# main_on_hydrolib.net
KiCad netlist of a schematic drawn in Altium Designer
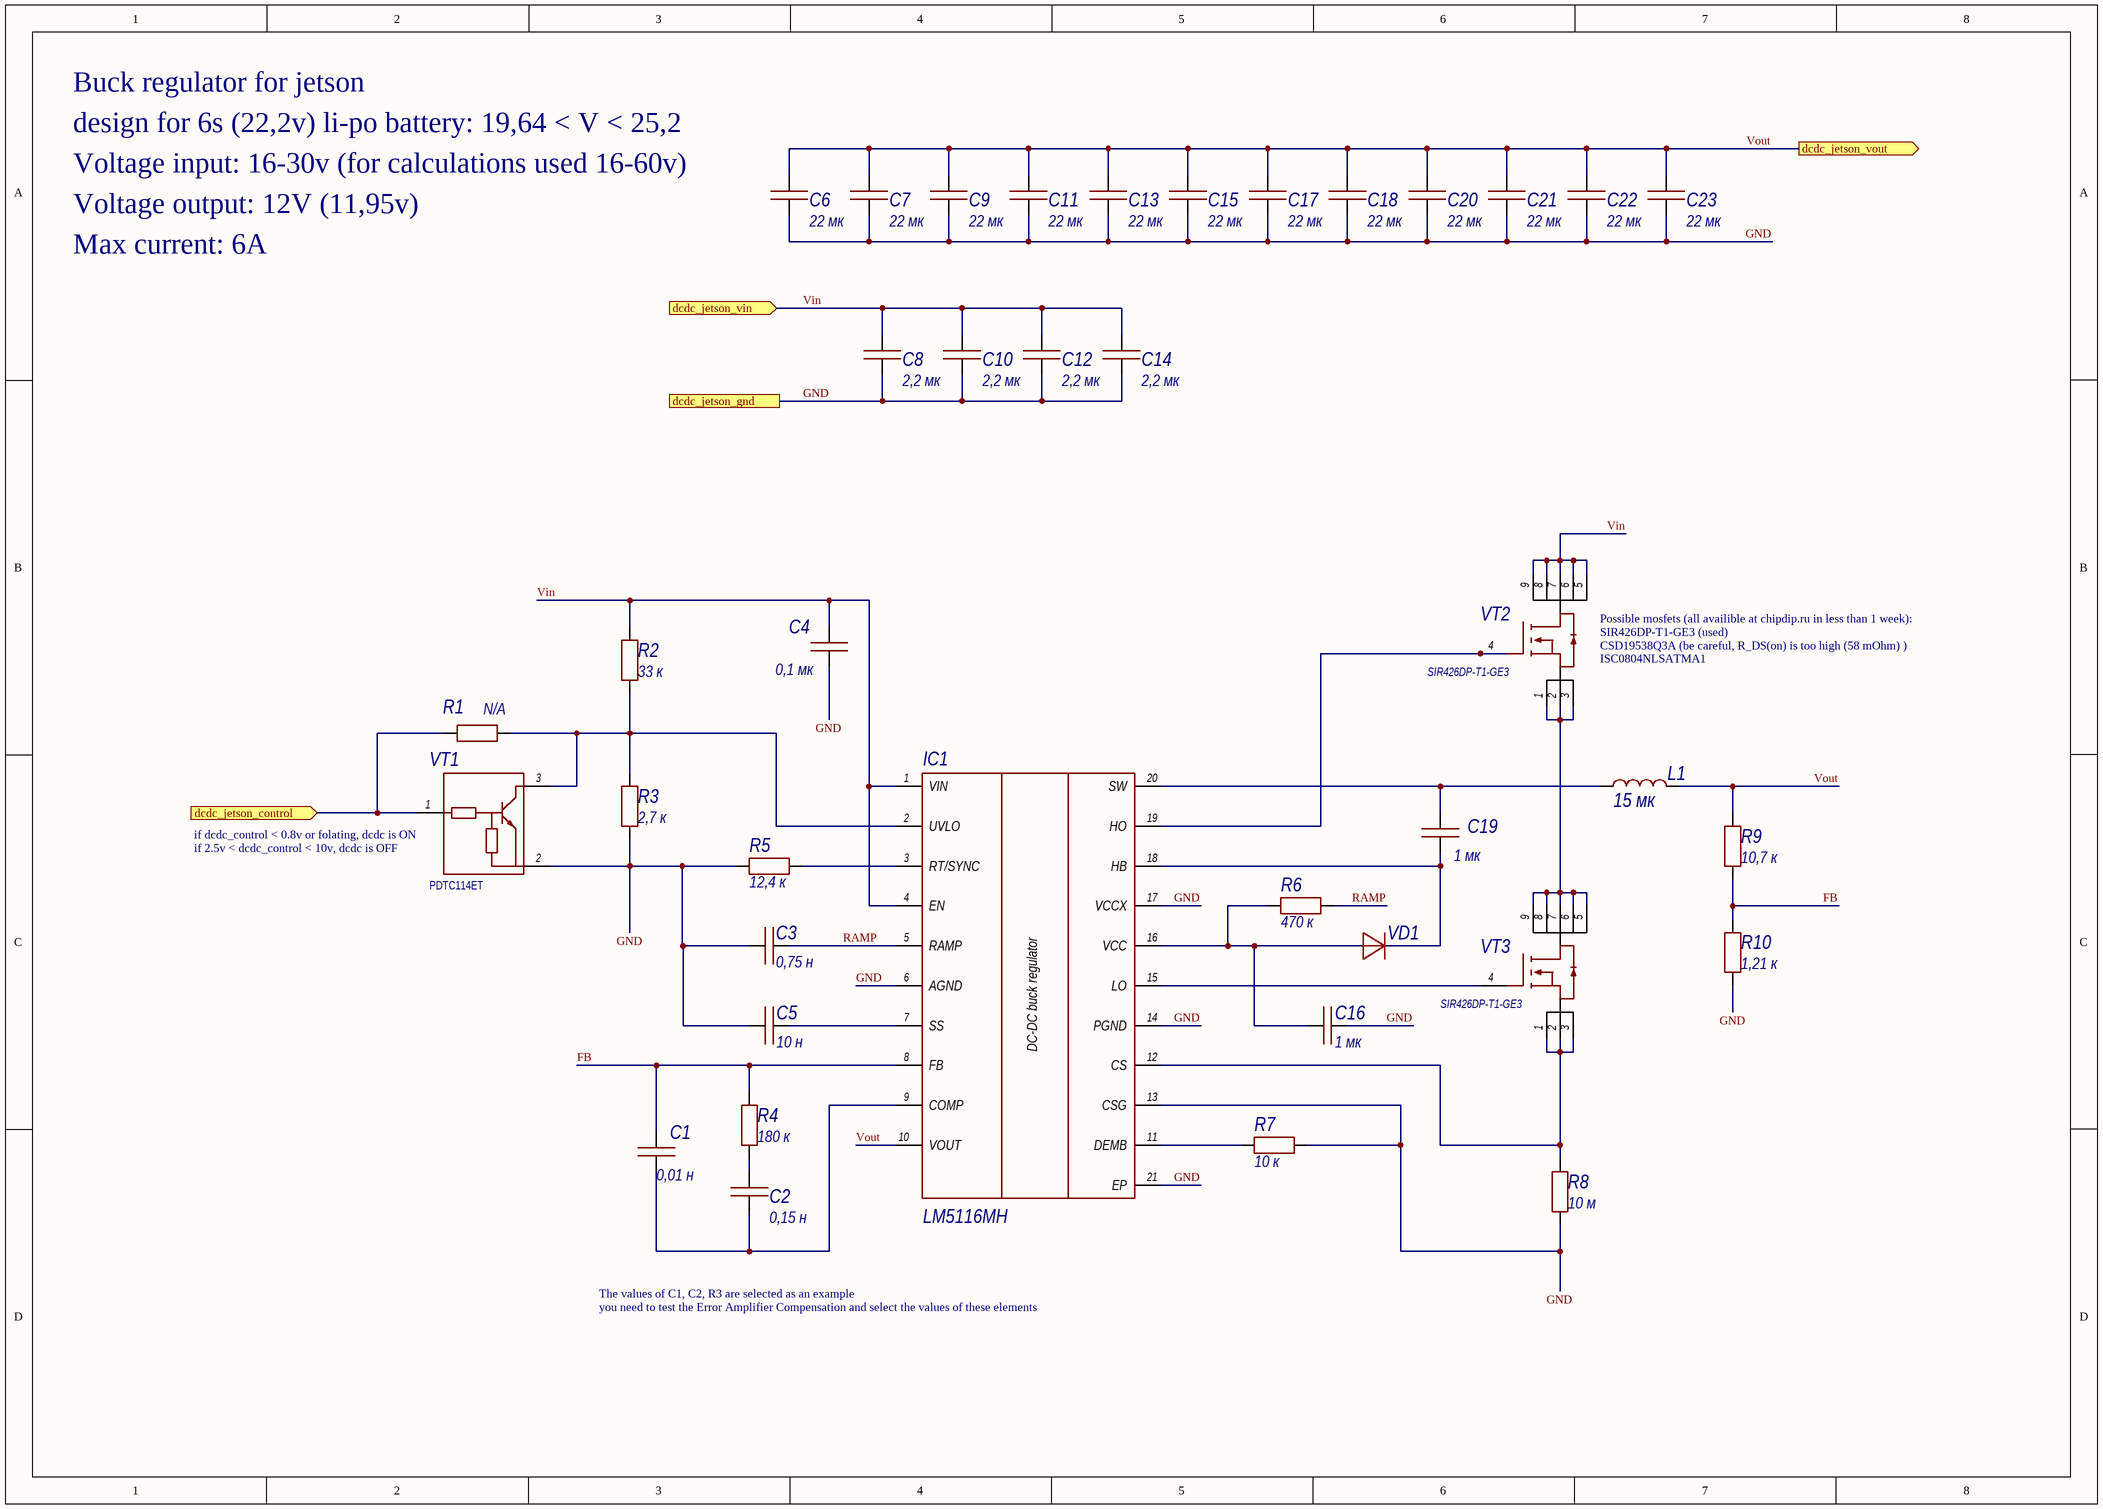
[diagram p0: main_on_hydrolib.SchDoc]

(export (version "E")
  (design (tool "Eeschema 10.0.6"))
  (components
    (comp (ref "C1")
      (value "0,01 н")
      (footprint "0603C")
      (description "Конденсатор")
      (fields
        (field (name "PART NUMBER") "Capacitor_0,01n_10_50V_X7R_0603C")
        (field (name "TOLERANCE") "0,1")
      )
      (libsource (lib "Hydrolib") (part "Capacitor"))
    )
    (comp (ref "C2")
      (value "0,15 н")
      (footprint "0603C")
      (description "Конденсатор")
      (fields
        (field (name "PART NUMBER") "Capacitor_0,15n_10_50V_X7R_0603C")
        (field (name "TOLERANCE") "0,1")
      )
      (libsource (lib "Hydrolib") (part "Capacitor"))
    )
    (comp (ref "C3")
      (value "0,75 н")
      (footprint "0603C")
      (description "Конденсатор")
      (fields
        (field (name "PART NUMBER") "Capacitor_0,75n_10_50V_X7R_0603C")
        (field (name "TOLERANCE") "0,1")
      )
      (libsource (lib "Hydrolib") (part "Capacitor"))
    )
    (comp (ref "C4")
      (value "0,1 мк")
      (footprint "0603C")
      (description "Конденсатор")
      (fields (field (name "PART NUMBER") "Capacitor_0,1u_10_50V_X7R_0603C") (field (name "TOLERANCE") "0,1"))
      (libsource (lib "Hydrolib") (part "Capacitor"))
    )
    (comp (ref "C5")
      (value "10 н")
      (footprint "0603C")
      (description "Конденсатор")
      (fields (field (name "PART NUMBER") "Capacitor_10n_10_50V_X7R_0603C") (field (name "TOLERANCE") "0,1"))
      (libsource (lib "Hydrolib") (part "Capacitor"))
    )
    (comp (ref "C6")
      (value "22 мк")
      (footprint "1210C")
      (description "Конденсатор")
      (fields (field (name "PART NUMBER") "Capacitor_22u_10_25V_X7R_1210C") (field (name "TOLERANCE") "0,1"))
      (libsource (lib "Hydrolib") (part "Capacitor"))
    )
    (comp (ref "C7")
      (value "22 мк")
      (footprint "1210C")
      (description "Конденсатор")
      (fields (field (name "PART NUMBER") "Capacitor_22u_10_25V_X7R_1210C") (field (name "TOLERANCE") "0,1"))
      (libsource (lib "Hydrolib") (part "Capacitor"))
    )
    (comp (ref "C8")
      (value "2,2 мк")
      (footprint "1206C")
      (description "Конденсатор")
      (fields (field (name "PART NUMBER") "Capacitor_2,2u_10_50V_X7R_1206C") (field (name "TOLERANCE") "0,1"))
      (libsource (lib "Hydrolib") (part "Capacitor"))
    )
    (comp (ref "C9")
      (value "22 мк")
      (footprint "1210C")
      (description "Конденсатор")
      (fields (field (name "PART NUMBER") "Capacitor_22u_10_25V_X7R_1210C") (field (name "TOLERANCE") "0,1"))
      (libsource (lib "Hydrolib") (part "Capacitor"))
    )
    (comp (ref "C10")
      (value "2,2 мк")
      (footprint "1206C")
      (description "Конденсатор")
      (fields (field (name "PART NUMBER") "Capacitor_2,2u_10_50V_X7R_1206C") (field (name "TOLERANCE") "0,1"))
      (libsource (lib "Hydrolib") (part "Capacitor"))
    )
    (comp (ref "C11")
      (value "22 мк")
      (footprint "1210C")
      (description "Конденсатор")
      (fields (field (name "PART NUMBER") "Capacitor_22u_10_25V_X7R_1210C") (field (name "TOLERANCE") "0,1"))
      (libsource (lib "Hydrolib") (part "Capacitor"))
    )
    (comp (ref "C12")
      (value "2,2 мк")
      (footprint "1206C")
      (description "Конденсатор")
      (fields (field (name "PART NUMBER") "Capacitor_2,2u_10_50V_X7R_1206C") (field (name "TOLERANCE") "0,1"))
      (libsource (lib "Hydrolib") (part "Capacitor"))
    )
    (comp (ref "C13")
      (value "22 мк")
      (footprint "1210C")
      (description "Конденсатор")
      (fields (field (name "PART NUMBER") "Capacitor_22u_10_25V_X7R_1210C") (field (name "TOLERANCE") "0,1"))
      (libsource (lib "Hydrolib") (part "Capacitor"))
    )
    (comp (ref "C14")
      (value "2,2 мк")
      (footprint "1206C")
      (description "Конденсатор")
      (fields (field (name "PART NUMBER") "Capacitor_2,2u_10_50V_X7R_1206C") (field (name "TOLERANCE") "0,1"))
      (libsource (lib "Hydrolib") (part "Capacitor"))
    )
    (comp (ref "C15")
      (value "22 мк")
      (footprint "1210C")
      (description "Конденсатор")
      (fields (field (name "PART NUMBER") "Capacitor_22u_10_25V_X7R_1210C") (field (name "TOLERANCE") "0,1"))
      (libsource (lib "Hydrolib") (part "Capacitor"))
    )
    (comp (ref "C16")
      (value "1 мк")
      (footprint "0603C")
      (description "Конденсатор")
      (fields (field (name "PART NUMBER") "Capacitor_1u_10_50V_X7R_0603C") (field (name "TOLERANCE") "0,1"))
      (libsource (lib "Hydrolib") (part "Capacitor"))
    )
    (comp (ref "C17")
      (value "22 мк")
      (footprint "1210C")
      (description "Конденсатор")
      (fields (field (name "PART NUMBER") "Capacitor_22u_10_25V_X7R_1210C") (field (name "TOLERANCE") "0,1"))
      (libsource (lib "Hydrolib") (part "Capacitor"))
    )
    (comp (ref "C18")
      (value "22 мк")
      (footprint "1210C")
      (description "Конденсатор")
      (fields (field (name "PART NUMBER") "Capacitor_22u_10_25V_X7R_1210C") (field (name "TOLERANCE") "0,1"))
      (libsource (lib "Hydrolib") (part "Capacitor"))
    )
    (comp (ref "C19")
      (value "1 мк")
      (footprint "0603C")
      (description "Конденсатор")
      (fields (field (name "PART NUMBER") "Capacitor_1u_10_50V_X7R_0603C") (field (name "TOLERANCE") "0,1"))
      (libsource (lib "Hydrolib") (part "Capacitor"))
    )
    (comp (ref "C20")
      (value "22 мк")
      (footprint "1210C")
      (description "Конденсатор")
      (fields (field (name "PART NUMBER") "Capacitor_22u_10_25V_X7R_1210C") (field (name "TOLERANCE") "0,1"))
      (libsource (lib "Hydrolib") (part "Capacitor"))
    )
    (comp (ref "C21")
      (value "22 мк")
      (footprint "1210C")
      (description "Конденсатор")
      (fields (field (name "PART NUMBER") "Capacitor_22u_10_25V_X7R_1210C") (field (name "TOLERANCE") "0,1"))
      (libsource (lib "Hydrolib") (part "Capacitor"))
    )
    (comp (ref "C22")
      (value "22 мк")
      (footprint "1210C")
      (description "Конденсатор")
      (fields (field (name "PART NUMBER") "Capacitor_22u_10_25V_X7R_1210C") (field (name "TOLERANCE") "0,1"))
      (libsource (lib "Hydrolib") (part "Capacitor"))
    )
    (comp (ref "C23")
      (value "22 мк")
      (footprint "1210C")
      (description "Конденсатор")
      (fields (field (name "PART NUMBER") "Capacitor_22u_10_25V_X7R_1210C") (field (name "TOLERANCE") "0,1"))
      (libsource (lib "Hydrolib") (part "Capacitor"))
    )
    (comp (ref "IC1")
      (value "LM5116MH")
      (footprint "SOP65P640X110-21N")
      (description "dc-dc понижающий adj 6-100v")
      (fields (field (name "MANUFACTURER_PART_NUMBER") "LM5116MH/NOPB"))
      (libsource (lib "Hydrolib") (part "LM5116MH"))
    )
    (comp (ref "L1")
      (value "15 мк")
      (footprint "SPRH127")
      (description "Индуктивность на 15 мкГн, номинальный ток 8,4 А")
      (fields (field (name "PART NUMBER") "CDSPRH127-150M"))
      (libsource (lib "Hydrolib") (part "Inductance"))
    )
    (comp (ref "R1")
      (value "N/A")
      (footprint "0603R")
      (description "посадочное место 0603 под перемычку")
      (fields (field (name "PART NUMBER") "res_0603_N/A") (field (name "TOLERANCE") "1%"))
      (libsource (lib "") (part "Resistor_1"))
    )
    (comp (ref "R2")
      (value "33 к")
      (footprint "0603R")
      (description "Резистор номиналом 33 кОм и точностью 1%")
      (fields (field (name "PART NUMBER") "Resistor_33k_1_0603") (field (name "TOLERANCE") "1%"))
      (libsource (lib "Hydrolib") (part "Resistor"))
    )
    (comp (ref "R3")
      (value "2,7 к")
      (footprint "0603R")
      (description "Резистор номиналом 2,7 кОм и точностью 1%")
      (fields (field (name "PART NUMBER") "Resistor_2.7k_1_0603") (field (name "TOLERANCE") "1%"))
      (libsource (lib "Hydrolib") (part "Resistor"))
    )
    (comp (ref "R4")
      (value "180 к")
      (footprint "0603R")
      (description "Резистор номиналом 180 кОм и точностью 1%")
      (fields (field (name "PART NUMBER") "Resistor_180k_1_0603") (field (name "TOLERANCE") "1%"))
      (libsource (lib "Hydrolib") (part "Resistor"))
    )
    (comp (ref "R5")
      (value "12,4 к")
      (footprint "0603R")
      (description "Резистор номиналом 12,4 кОм и точностью 1%")
      (fields (field (name "PART NUMBER") "Resistor_12.4k_1_0603") (field (name "TOLERANCE") "1%"))
      (libsource (lib "") (part "Resistor_1"))
    )
    (comp (ref "R6")
      (value "470 к")
      (footprint "0603R")
      (description "Резистор номиналом 470 кОм и точностью 1%")
      (fields (field (name "PART NUMBER") "Resistor_470k_1_0603") (field (name "TOLERANCE") "1%"))
      (libsource (lib "") (part "Resistor_1"))
    )
    (comp (ref "R7")
      (value "10 к")
      (footprint "0603R")
      (description "Резистор номиналом 10 кОм и точностью 1%")
      (fields (field (name "PART NUMBER") "Resistor_10k_1_0603") (field (name "TOLERANCE") "1%"))
      (libsource (lib "") (part "Resistor_1"))
    )
    (comp (ref "R8")
      (value "10 м")
      (footprint "1210R")
      (description "Резистор номиналом 10 мОм, точностью 1%, 0.5Вт")
      (fields (field (name "PART NUMBER") "RL1210FR-070R01L") (field (name "TOLERANCE") "1%"))
      (libsource (lib "Hydrolib") (part "Resistor"))
    )
    (comp (ref "R9")
      (value "10,7 к")
      (footprint "0603R")
      (description "Резистор номиналом 10,7 кОм и точностью 1%")
      (fields (field (name "PART NUMBER") "Resistor_10.7k_1_0603") (field (name "TOLERANCE") "1%"))
      (libsource (lib "Hydrolib") (part "Resistor"))
    )
    (comp (ref "R10")
      (value "1,21 к")
      (footprint "0603R")
      (description "Резистор номиналом 1,21 кОм и точностью 1%")
      (fields (field (name "PART NUMBER") "Resistor_1.21k_1_0603") (field (name "TOLERANCE") "1%"))
      (libsource (lib "Hydrolib") (part "Resistor"))
    )
    (comp (ref "VD1")
      (value "ES1D-E3/61T")
      (footprint "SMA")
      (description "Диод 1A 200V")
      (libsource (lib "Hydrolib") (part "Rectifier_diode"))
    )
    (comp (ref "VT1")
      (value "PDTC114ET")
      (footprint "SOT23-3")
      (description "цифровой npn 50в 100мА")
      (libsource (lib "Hydrolib") (part "PDTC114ET"))
    )
    (comp (ref "VT2")
      (value "SIR426DP-T1-GE3")
      (footprint "PowerPAK_SO-8")
      (description "Транзистор полевой MOSFET N-канальный 40В 41.7Вт")
      (libsource (lib "Hydrolib") (part "SIR426DP-T1-GE3"))
    )
    (comp (ref "VT3")
      (value "SIR426DP-T1-GE3")
      (footprint "PowerPAK_SO-8")
      (description "Транзистор полевой MOSFET N-канальный 40В 41.7Вт")
      (libsource (lib "Hydrolib") (part "SIR426DP-T1-GE3"))
    )
  )
  (nets
    (net (code "1") (name "/FB") (class "Default")
      (node (ref "C1") (pin "2") (pinfunction "2_2") (pintype "passive"))
      (node (ref "IC1") (pin "8") (pinfunction "FB_8") (pintype "passive"))
      (node (ref "R10") (pin "2") (pinfunction "2_2") (pintype "passive"))
      (node (ref "R4") (pin "2") (pinfunction "2_2") (pintype "passive"))
      (node (ref "R9") (pin "1") (pinfunction "1_1") (pintype "passive"))
    )
    (net (code "2") (name "/GND") (class "Default")
      (node (ref "C10") (pin "1") (pinfunction "1_1") (pintype "passive"))
      (node (ref "C11") (pin "1") (pinfunction "1_1") (pintype "passive"))
      (node (ref "C12") (pin "1") (pinfunction "1_1") (pintype "passive"))
      (node (ref "C13") (pin "1") (pinfunction "1_1") (pintype "passive"))
      (node (ref "C14") (pin "1") (pinfunction "1_1") (pintype "passive"))
      (node (ref "C15") (pin "1") (pinfunction "1_1") (pintype "passive"))
      (node (ref "C16") (pin "2") (pinfunction "2_2") (pintype "passive"))
      (node (ref "C17") (pin "1") (pinfunction "1_1") (pintype "passive"))
      (node (ref "C18") (pin "1") (pinfunction "1_1") (pintype "passive"))
      (node (ref "C20") (pin "1") (pinfunction "1_1") (pintype "passive"))
      (node (ref "C21") (pin "1") (pinfunction "1_1") (pintype "passive"))
      (node (ref "C22") (pin "1") (pinfunction "1_1") (pintype "passive"))
      (node (ref "C23") (pin "1") (pinfunction "1_1") (pintype "passive"))
      (node (ref "C3") (pin "1") (pinfunction "1_1") (pintype "passive"))
      (node (ref "C4") (pin "1") (pinfunction "1_1") (pintype "passive"))
      (node (ref "C5") (pin "1") (pinfunction "1_1") (pintype "passive"))
      (node (ref "C6") (pin "1") (pinfunction "1_1") (pintype "passive"))
      (node (ref "C7") (pin "1") (pinfunction "1_1") (pintype "passive"))
      (node (ref "C8") (pin "1") (pinfunction "1_1") (pintype "passive"))
      (node (ref "C9") (pin "1") (pinfunction "1_1") (pintype "passive"))
      (node (ref "IC1") (pin "13") (pinfunction "CSG_13") (pintype "passive"))
      (node (ref "IC1") (pin "14") (pinfunction "PGND_14") (pintype "passive"))
      (node (ref "IC1") (pin "17") (pinfunction "VCCX_17") (pintype "passive"))
      (node (ref "IC1") (pin "21") (pinfunction "EP_21") (pintype "passive"))
      (node (ref "IC1") (pin "6") (pinfunction "AGND_6") (pintype "passive"))
      (node (ref "R10") (pin "1") (pinfunction "1_1") (pintype "passive"))
      (node (ref "R3") (pin "1") (pinfunction "1_1") (pintype "passive"))
      (node (ref "R5") (pin "1") (pinfunction "1_1") (pintype "passive"))
      (node (ref "R7") (pin "2") (pinfunction "2_2") (pintype "passive"))
      (node (ref "R8") (pin "1") (pinfunction "1_1") (pintype "passive"))
      (node (ref "VT1") (pin "2") (pinfunction "E_2") (pintype "passive"))
    )
    (net (code "3") (name "/RAMP") (class "Default")
      (node (ref "C3") (pin "2") (pinfunction "2_2") (pintype "passive"))
      (node (ref "IC1") (pin "5") (pinfunction "RAMP_5") (pintype "passive"))
      (node (ref "R6") (pin "2") (pinfunction "2_2") (pintype "passive"))
    )
    (net (code "4") (name "/Vin") (class "Default")
      (node (ref "C10") (pin "2") (pinfunction "2_2") (pintype "passive"))
      (node (ref "C12") (pin "2") (pinfunction "2_2") (pintype "passive"))
      (node (ref "C14") (pin "2") (pinfunction "2_2") (pintype "passive"))
      (node (ref "C4") (pin "2") (pinfunction "2_2") (pintype "passive"))
      (node (ref "C8") (pin "2") (pinfunction "2_2") (pintype "passive"))
      (node (ref "IC1") (pin "1") (pinfunction "VIN_1") (pintype "passive"))
      (node (ref "IC1") (pin "4") (pinfunction "EN_4") (pintype "passive"))
      (node (ref "R2") (pin "2") (pinfunction "2_2") (pintype "passive"))
      (node (ref "VT2") (pin "5") (pinfunction "5_5") (pintype "passive"))
      (node (ref "VT2") (pin "6") (pinfunction "6_6") (pintype "passive"))
      (node (ref "VT2") (pin "7") (pinfunction "7_7") (pintype "passive"))
      (node (ref "VT2") (pin "8") (pinfunction "8_8") (pintype "passive"))
      (node (ref "VT2") (pin "9") (pinfunction "9_9") (pintype "passive"))
    )
    (net (code "5") (name "/Vout") (class "Default")
      (node (ref "C11") (pin "2") (pinfunction "2_2") (pintype "passive"))
      (node (ref "C13") (pin "2") (pinfunction "2_2") (pintype "passive"))
      (node (ref "C15") (pin "2") (pinfunction "2_2") (pintype "passive"))
      (node (ref "C17") (pin "2") (pinfunction "2_2") (pintype "passive"))
      (node (ref "C18") (pin "2") (pinfunction "2_2") (pintype "passive"))
      (node (ref "C20") (pin "2") (pinfunction "2_2") (pintype "passive"))
      (node (ref "C21") (pin "2") (pinfunction "2_2") (pintype "passive"))
      (node (ref "C22") (pin "2") (pinfunction "2_2") (pintype "passive"))
      (node (ref "C23") (pin "2") (pinfunction "2_2") (pintype "passive"))
      (node (ref "C6") (pin "2") (pinfunction "2_2") (pintype "passive"))
      (node (ref "C7") (pin "2") (pinfunction "2_2") (pintype "passive"))
      (node (ref "C9") (pin "2") (pinfunction "2_2") (pintype "passive"))
      (node (ref "IC1") (pin "10") (pinfunction "VOUT_10") (pintype "passive"))
      (node (ref "L1") (pin "2") (pinfunction "2_2") (pintype "passive"))
      (node (ref "R9") (pin "2") (pinfunction "2_2") (pintype "passive"))
    )
    (net (code "6") (name "/dcdc_jetson_control") (class "Default")
      (node (ref "R1") (pin "1") (pinfunction "1_1") (pintype "passive"))
      (node (ref "VT1") (pin "1") (pinfunction "B_1") (pintype "passive"))
    )
    (net (code "7") (name "Net-(C2-Pad2)") (class "Default")
      (node (ref "C2") (pin "2") (pinfunction "2_2") (pintype "passive"))
      (node (ref "R4") (pin "1") (pinfunction "1_1") (pintype "passive"))
    )
    (net (code "8") (name "Net-(IC1-COMP)") (class "Default")
      (node (ref "C1") (pin "1") (pinfunction "1_1") (pintype "passive"))
      (node (ref "C2") (pin "1") (pinfunction "1_1") (pintype "passive"))
      (node (ref "IC1") (pin "9") (pinfunction "COMP_9") (pintype "passive"))
    )
    (net (code "9") (name "Net-(IC1-CS)") (class "Default")
      (node (ref "IC1") (pin "12") (pinfunction "CS_12") (pintype "passive"))
      (node (ref "R8") (pin "2") (pinfunction "2_2") (pintype "passive"))
      (node (ref "VT3") (pin "1") (pinfunction "1_1") (pintype "passive"))
      (node (ref "VT3") (pin "2") (pinfunction "2_2") (pintype "passive"))
      (node (ref "VT3") (pin "3") (pinfunction "3_3") (pintype "passive"))
    )
    (net (code "10") (name "Net-(IC1-DEMB)") (class "Default")
      (node (ref "IC1") (pin "11") (pinfunction "DEMB_11") (pintype "passive"))
      (node (ref "R7") (pin "1") (pinfunction "1_1") (pintype "passive"))
    )
    (net (code "11") (name "Net-(IC1-HB)") (class "Default")
      (node (ref "C19") (pin "1") (pinfunction "1_1") (pintype "passive"))
      (node (ref "IC1") (pin "18") (pinfunction "HB_18") (pintype "passive"))
      (node (ref "VD1") (pin "2") (pinfunction "2_2") (pintype "passive"))
    )
    (net (code "12") (name "Net-(IC1-HO)") (class "Default")
      (node (ref "IC1") (pin "19") (pinfunction "HO_19") (pintype "passive"))
      (node (ref "VT2") (pin "4") (pinfunction "4_4") (pintype "passive"))
    )
    (net (code "13") (name "Net-(IC1-LO)") (class "Default")
      (node (ref "IC1") (pin "15") (pinfunction "LO_15") (pintype "passive"))
      (node (ref "VT3") (pin "4") (pinfunction "4_4") (pintype "passive"))
    )
    (net (code "14") (name "Net-(IC1-RT{slash}SYNC)") (class "Default")
      (node (ref "IC1") (pin "3") (pinfunction "RT/SYNC_3") (pintype "passive"))
      (node (ref "R5") (pin "2") (pinfunction "2_2") (pintype "passive"))
    )
    (net (code "15") (name "Net-(IC1-SS)") (class "Default")
      (node (ref "C5") (pin "2") (pinfunction "2_2") (pintype "passive"))
      (node (ref "IC1") (pin "7") (pinfunction "SS_7") (pintype "passive"))
    )
    (net (code "16") (name "Net-(IC1-SW)") (class "Default")
      (node (ref "C19") (pin "2") (pinfunction "2_2") (pintype "passive"))
      (node (ref "IC1") (pin "20") (pinfunction "SW_20") (pintype "passive"))
      (node (ref "L1") (pin "1") (pinfunction "1_1") (pintype "passive"))
    )
    (net (code "17") (name "Net-(IC1-UVLO)") (class "Default")
      (node (ref "IC1") (pin "2") (pinfunction "UVLO_2") (pintype "passive"))
      (node (ref "R1") (pin "2") (pinfunction "2_2") (pintype "passive"))
      (node (ref "R2") (pin "1") (pinfunction "1_1") (pintype "passive"))
      (node (ref "R3") (pin "2") (pinfunction "2_2") (pintype "passive"))
      (node (ref "VT1") (pin "3") (pinfunction "C_3") (pintype "passive"))
    )
    (net (code "18") (name "Net-(IC1-VCC)") (class "Default")
      (node (ref "C16") (pin "1") (pinfunction "1_1") (pintype "passive"))
      (node (ref "IC1") (pin "16") (pinfunction "VCC_16") (pintype "passive"))
      (node (ref "R6") (pin "1") (pinfunction "1_1") (pintype "passive"))
      (node (ref "VD1") (pin "1") (pinfunction "1_1") (pintype "passive"))
    )
    (net (code "19") (name "Net-(VT2-Pad1)") (class "Default")
      (node (ref "VT2") (pin "1") (pinfunction "1_1") (pintype "passive"))
      (node (ref "VT2") (pin "2") (pinfunction "2_2") (pintype "passive"))
      (node (ref "VT2") (pin "3") (pinfunction "3_3") (pintype "passive"))
      (node (ref "VT3") (pin "5") (pinfunction "5_5") (pintype "passive"))
      (node (ref "VT3") (pin "6") (pinfunction "6_6") (pintype "passive"))
      (node (ref "VT3") (pin "7") (pinfunction "7_7") (pintype "passive"))
      (node (ref "VT3") (pin "8") (pinfunction "8_8") (pintype "passive"))
      (node (ref "VT3") (pin "9") (pinfunction "9_9") (pintype "passive"))
    )
  )
)
